# SDRAM.net
KiCad netlist of a schematic drawn in Altium Designer
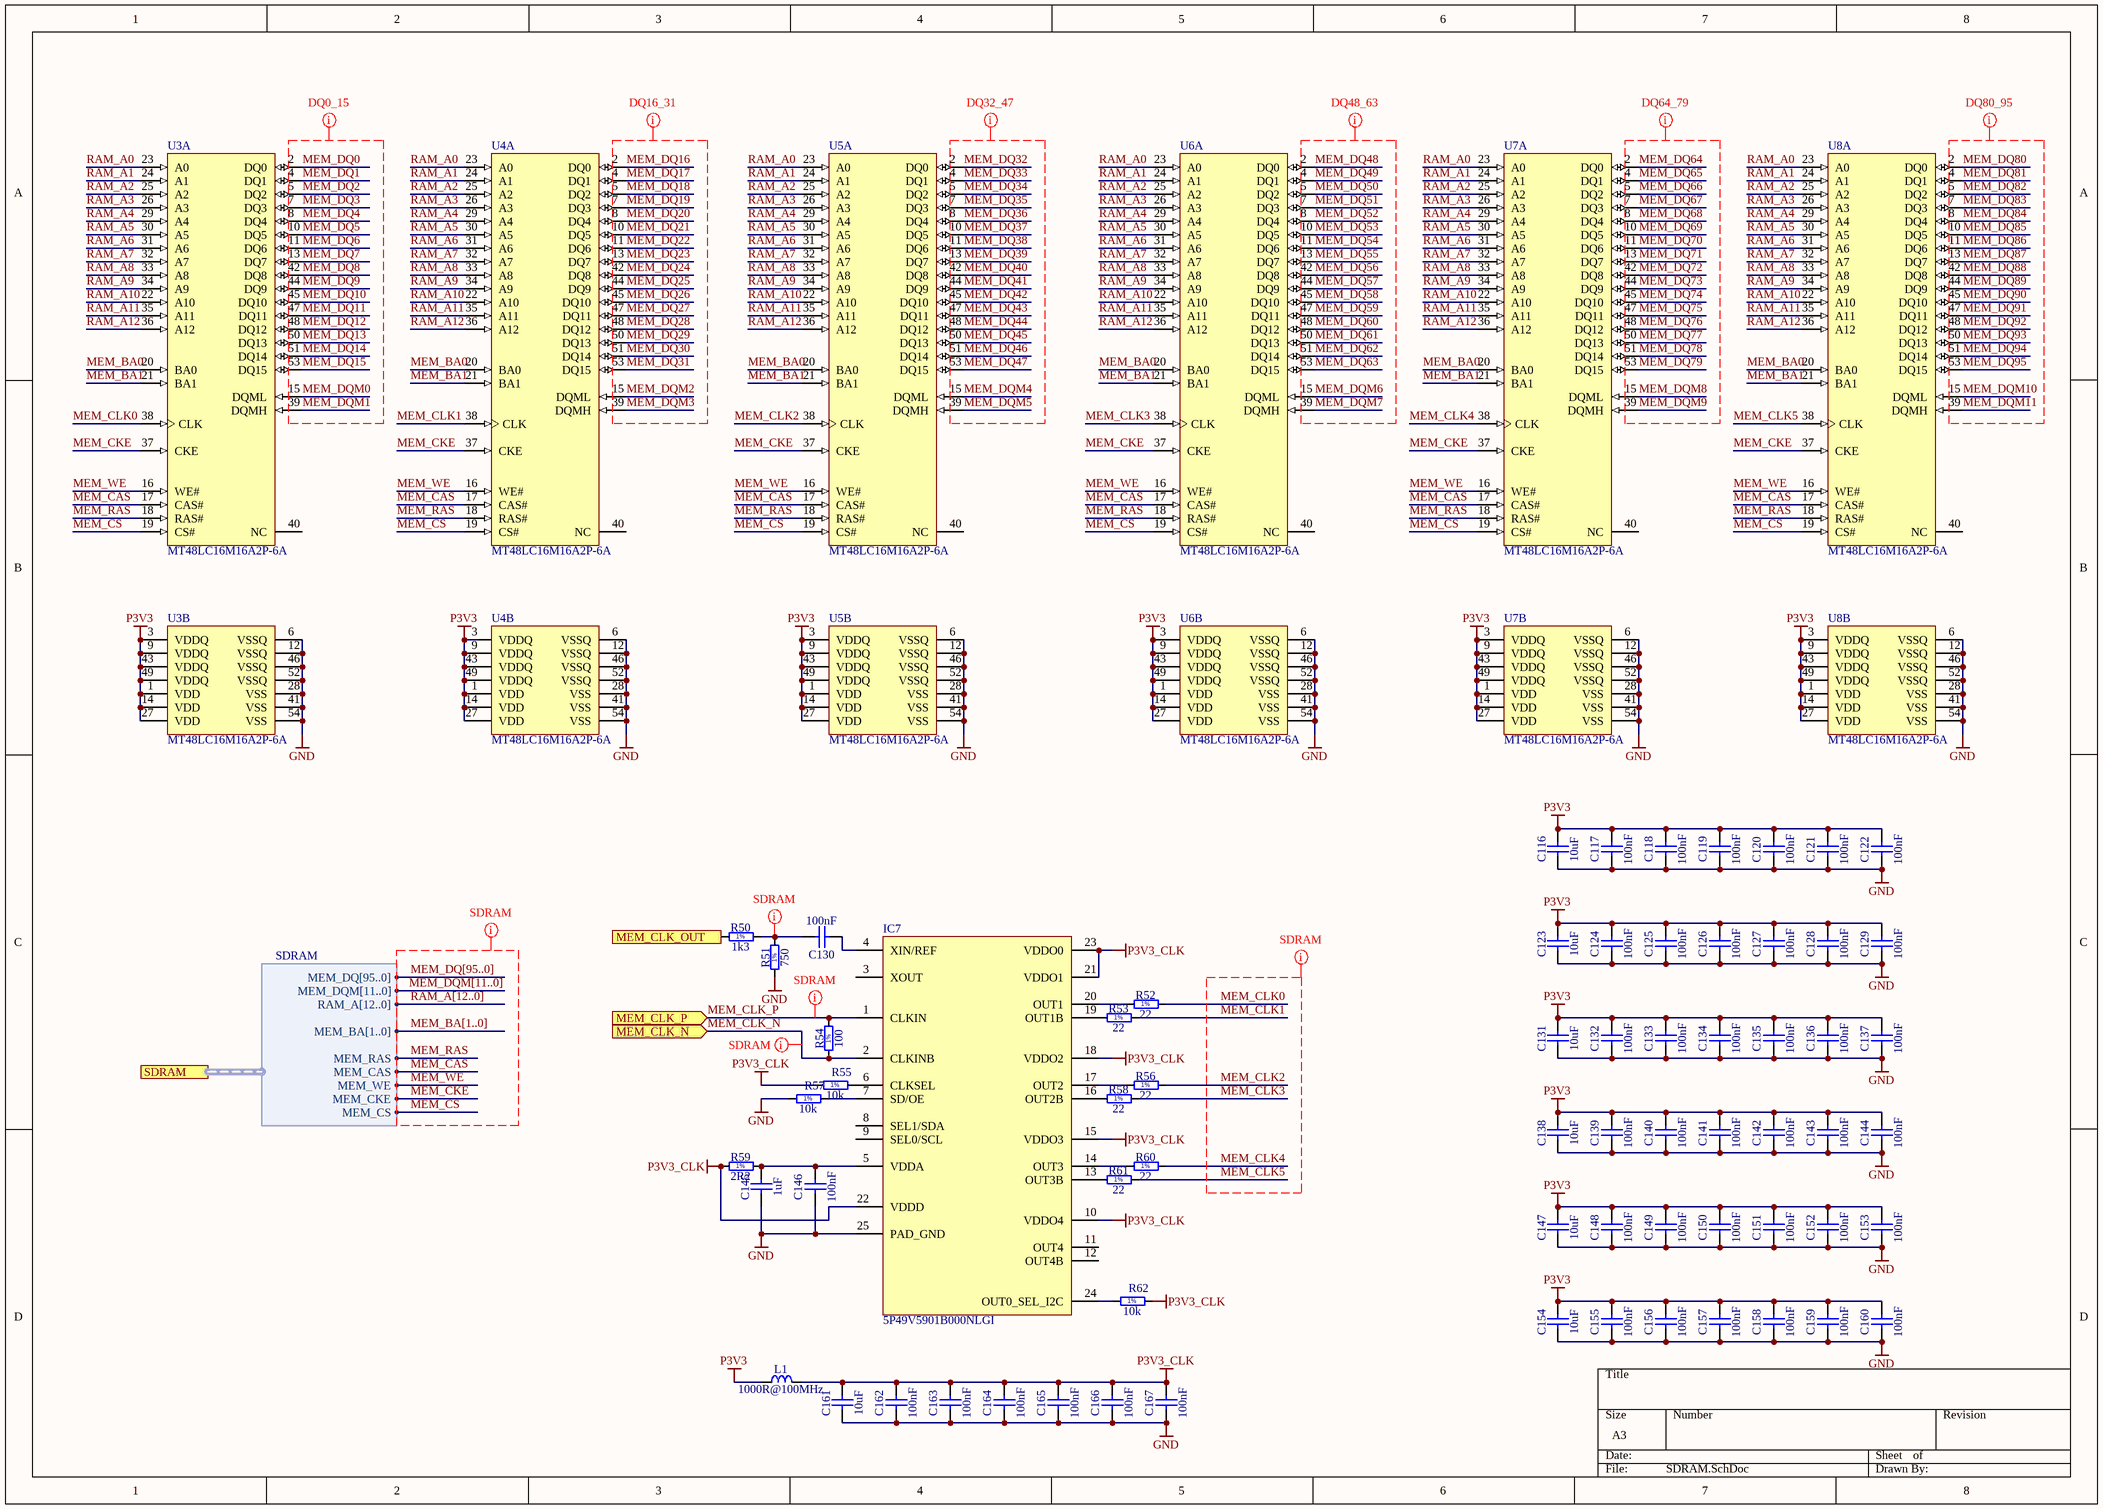
[diagram p0: SDRAM.SchDoc]

(export (version "E")
  (design (tool "Eeschema 10.0.6"))
  (components
    (comp (ref "C116")
      (value "10uF")
      (footprint "CAPC2012X135N")
      (description "Non-polarised capacitor")
      (fields
        (field (name "PART NUMBER") "CC0805_10UF_16V_10%_X5R")
        (field (name "VOLTAGE") "16V")
        (field (name "AUTHOR") "CERN DEM JLC")
      )
      (libsource (lib "Capacitors") (part "Capacitor - non polarized"))
    )
    (comp (ref "C117")
      (value "100nF")
      (footprint "CAPC0603X33N")
      (description "Non-polarised capacitor")
      (fields
        (field (name "MANUFACTURER") "GENERIC")
        (field (name "PART NUMBER") "CC0201_100NF_6.3V_10%_X5R")
        (field (name "AUTHOR") "CERN DEM JLC")
      )
      (libsource (lib "Capacitors") (part "Capacitor - non polarized"))
    )
    (comp (ref "C118")
      (value "100nF")
      (footprint "CAPC0603X33N")
      (description "Non-polarised capacitor")
      (fields
        (field (name "MANUFACTURER") "GENERIC")
        (field (name "PART NUMBER") "CC0201_100NF_6.3V_10%_X5R")
        (field (name "AUTHOR") "CERN DEM JLC")
      )
      (libsource (lib "Capacitors") (part "Capacitor - non polarized"))
    )
    (comp (ref "C119")
      (value "100nF")
      (footprint "CAPC0603X33N")
      (description "Non-polarised capacitor")
      (fields
        (field (name "MANUFACTURER") "GENERIC")
        (field (name "PART NUMBER") "CC0201_100NF_6.3V_10%_X5R")
        (field (name "AUTHOR") "CERN DEM JLC")
      )
      (libsource (lib "Capacitors") (part "Capacitor - non polarized"))
    )
    (comp (ref "C120")
      (value "100nF")
      (footprint "CAPC0603X33N")
      (description "Non-polarised capacitor")
      (fields
        (field (name "MANUFACTURER") "GENERIC")
        (field (name "PART NUMBER") "CC0201_100NF_6.3V_10%_X5R")
        (field (name "AUTHOR") "CERN DEM JLC")
      )
      (libsource (lib "Capacitors") (part "Capacitor - non polarized"))
    )
    (comp (ref "C121")
      (value "100nF")
      (footprint "CAPC0603X33N")
      (description "Non-polarised capacitor")
      (fields
        (field (name "MANUFACTURER") "GENERIC")
        (field (name "PART NUMBER") "CC0201_100NF_6.3V_10%_X5R")
        (field (name "AUTHOR") "CERN DEM JLC")
      )
      (libsource (lib "Capacitors") (part "Capacitor - non polarized"))
    )
    (comp (ref "C122")
      (value "100nF")
      (footprint "CAPC0603X33N")
      (description "Non-polarised capacitor")
      (fields
        (field (name "MANUFACTURER") "GENERIC")
        (field (name "PART NUMBER") "CC0201_100NF_6.3V_10%_X5R")
        (field (name "AUTHOR") "CERN DEM JLC")
      )
      (libsource (lib "Capacitors") (part "Capacitor - non polarized"))
    )
    (comp (ref "C123")
      (value "10uF")
      (footprint "CAPC2012X135N")
      (description "Non-polarised capacitor")
      (fields
        (field (name "PART NUMBER") "CC0805_10UF_16V_10%_X5R")
        (field (name "VOLTAGE") "16V")
        (field (name "AUTHOR") "CERN DEM JLC")
      )
      (libsource (lib "Capacitors") (part "Capacitor - non polarized"))
    )
    (comp (ref "C124")
      (value "100nF")
      (footprint "CAPC0603X33N")
      (description "Non-polarised capacitor")
      (fields
        (field (name "MANUFACTURER") "GENERIC")
        (field (name "PART NUMBER") "CC0201_100NF_6.3V_10%_X5R")
        (field (name "AUTHOR") "CERN DEM JLC")
      )
      (libsource (lib "Capacitors") (part "Capacitor - non polarized"))
    )
    (comp (ref "C125")
      (value "100nF")
      (footprint "CAPC0603X33N")
      (description "Non-polarised capacitor")
      (fields
        (field (name "MANUFACTURER") "GENERIC")
        (field (name "PART NUMBER") "CC0201_100NF_6.3V_10%_X5R")
        (field (name "AUTHOR") "CERN DEM JLC")
      )
      (libsource (lib "Capacitors") (part "Capacitor - non polarized"))
    )
    (comp (ref "C126")
      (value "100nF")
      (footprint "CAPC0603X33N")
      (description "Non-polarised capacitor")
      (fields
        (field (name "MANUFACTURER") "GENERIC")
        (field (name "PART NUMBER") "CC0201_100NF_6.3V_10%_X5R")
        (field (name "AUTHOR") "CERN DEM JLC")
      )
      (libsource (lib "Capacitors") (part "Capacitor - non polarized"))
    )
    (comp (ref "C127")
      (value "100nF")
      (footprint "CAPC0603X33N")
      (description "Non-polarised capacitor")
      (fields
        (field (name "MANUFACTURER") "GENERIC")
        (field (name "PART NUMBER") "CC0201_100NF_6.3V_10%_X5R")
        (field (name "AUTHOR") "CERN DEM JLC")
      )
      (libsource (lib "Capacitors") (part "Capacitor - non polarized"))
    )
    (comp (ref "C128")
      (value "100nF")
      (footprint "CAPC0603X33N")
      (description "Non-polarised capacitor")
      (fields
        (field (name "MANUFACTURER") "GENERIC")
        (field (name "PART NUMBER") "CC0201_100NF_6.3V_10%_X5R")
        (field (name "AUTHOR") "CERN DEM JLC")
      )
      (libsource (lib "Capacitors") (part "Capacitor - non polarized"))
    )
    (comp (ref "C129")
      (value "100nF")
      (footprint "CAPC0603X33N")
      (description "Non-polarised capacitor")
      (fields
        (field (name "MANUFACTURER") "GENERIC")
        (field (name "PART NUMBER") "CC0201_100NF_6.3V_10%_X5R")
        (field (name "AUTHOR") "CERN DEM JLC")
      )
      (libsource (lib "Capacitors") (part "Capacitor - non polarized"))
    )
    (comp (ref "C130")
      (value "100nF")
      (footprint "CAPC0603X33N")
      (description "Non-polarised capacitor")
      (fields
        (field (name "MANUFACTURER") "GENERIC")
        (field (name "PART NUMBER") "CC0201_100NF_6.3V_10%_X5R")
        (field (name "AUTHOR") "CERN DEM JLC")
      )
      (libsource (lib "Capacitors") (part "Capacitor - non polarized"))
    )
    (comp (ref "C131")
      (value "10uF")
      (footprint "CAPC2012X135N")
      (description "Non-polarised capacitor")
      (fields
        (field (name "PART NUMBER") "CC0805_10UF_16V_10%_X5R")
        (field (name "VOLTAGE") "16V")
        (field (name "AUTHOR") "CERN DEM JLC")
      )
      (libsource (lib "Capacitors") (part "Capacitor - non polarized"))
    )
    (comp (ref "C132")
      (value "100nF")
      (footprint "CAPC0603X33N")
      (description "Non-polarised capacitor")
      (fields
        (field (name "MANUFACTURER") "GENERIC")
        (field (name "PART NUMBER") "CC0201_100NF_6.3V_10%_X5R")
        (field (name "AUTHOR") "CERN DEM JLC")
      )
      (libsource (lib "Capacitors") (part "Capacitor - non polarized"))
    )
    (comp (ref "C133")
      (value "100nF")
      (footprint "CAPC0603X33N")
      (description "Non-polarised capacitor")
      (fields
        (field (name "MANUFACTURER") "GENERIC")
        (field (name "PART NUMBER") "CC0201_100NF_6.3V_10%_X5R")
        (field (name "AUTHOR") "CERN DEM JLC")
      )
      (libsource (lib "Capacitors") (part "Capacitor - non polarized"))
    )
    (comp (ref "C134")
      (value "100nF")
      (footprint "CAPC0603X33N")
      (description "Non-polarised capacitor")
      (fields
        (field (name "MANUFACTURER") "GENERIC")
        (field (name "PART NUMBER") "CC0201_100NF_6.3V_10%_X5R")
        (field (name "AUTHOR") "CERN DEM JLC")
      )
      (libsource (lib "Capacitors") (part "Capacitor - non polarized"))
    )
    (comp (ref "C135")
      (value "100nF")
      (footprint "CAPC0603X33N")
      (description "Non-polarised capacitor")
      (fields
        (field (name "MANUFACTURER") "GENERIC")
        (field (name "PART NUMBER") "CC0201_100NF_6.3V_10%_X5R")
        (field (name "AUTHOR") "CERN DEM JLC")
      )
      (libsource (lib "Capacitors") (part "Capacitor - non polarized"))
    )
    (comp (ref "C136")
      (value "100nF")
      (footprint "CAPC0603X33N")
      (description "Non-polarised capacitor")
      (fields
        (field (name "MANUFACTURER") "GENERIC")
        (field (name "PART NUMBER") "CC0201_100NF_6.3V_10%_X5R")
        (field (name "AUTHOR") "CERN DEM JLC")
      )
      (libsource (lib "Capacitors") (part "Capacitor - non polarized"))
    )
    (comp (ref "C137")
      (value "100nF")
      (footprint "CAPC0603X33N")
      (description "Non-polarised capacitor")
      (fields
        (field (name "MANUFACTURER") "GENERIC")
        (field (name "PART NUMBER") "CC0201_100NF_6.3V_10%_X5R")
        (field (name "AUTHOR") "CERN DEM JLC")
      )
      (libsource (lib "Capacitors") (part "Capacitor - non polarized"))
    )
    (comp (ref "C138")
      (value "10uF")
      (footprint "CAPC2012X135N")
      (description "Non-polarised capacitor")
      (fields
        (field (name "PART NUMBER") "CC0805_10UF_16V_10%_X5R")
        (field (name "VOLTAGE") "16V")
        (field (name "AUTHOR") "CERN DEM JLC")
      )
      (libsource (lib "Capacitors") (part "Capacitor - non polarized"))
    )
    (comp (ref "C139")
      (value "100nF")
      (footprint "CAPC0603X33N")
      (description "Non-polarised capacitor")
      (fields
        (field (name "MANUFACTURER") "GENERIC")
        (field (name "PART NUMBER") "CC0201_100NF_6.3V_10%_X5R")
        (field (name "AUTHOR") "CERN DEM JLC")
      )
      (libsource (lib "Capacitors") (part "Capacitor - non polarized"))
    )
    (comp (ref "C140")
      (value "100nF")
      (footprint "CAPC0603X33N")
      (description "Non-polarised capacitor")
      (fields
        (field (name "MANUFACTURER") "GENERIC")
        (field (name "PART NUMBER") "CC0201_100NF_6.3V_10%_X5R")
        (field (name "AUTHOR") "CERN DEM JLC")
      )
      (libsource (lib "Capacitors") (part "Capacitor - non polarized"))
    )
    (comp (ref "C141")
      (value "100nF")
      (footprint "CAPC0603X33N")
      (description "Non-polarised capacitor")
      (fields
        (field (name "MANUFACTURER") "GENERIC")
        (field (name "PART NUMBER") "CC0201_100NF_6.3V_10%_X5R")
        (field (name "AUTHOR") "CERN DEM JLC")
      )
      (libsource (lib "Capacitors") (part "Capacitor - non polarized"))
    )
    (comp (ref "C142")
      (value "100nF")
      (footprint "CAPC0603X33N")
      (description "Non-polarised capacitor")
      (fields
        (field (name "MANUFACTURER") "GENERIC")
        (field (name "PART NUMBER") "CC0201_100NF_6.3V_10%_X5R")
        (field (name "AUTHOR") "CERN DEM JLC")
      )
      (libsource (lib "Capacitors") (part "Capacitor - non polarized"))
    )
    (comp (ref "C143")
      (value "100nF")
      (footprint "CAPC0603X33N")
      (description "Non-polarised capacitor")
      (fields
        (field (name "MANUFACTURER") "GENERIC")
        (field (name "PART NUMBER") "CC0201_100NF_6.3V_10%_X5R")
        (field (name "AUTHOR") "CERN DEM JLC")
      )
      (libsource (lib "Capacitors") (part "Capacitor - non polarized"))
    )
    (comp (ref "C144")
      (value "100nF")
      (footprint "CAPC0603X33N")
      (description "Non-polarised capacitor")
      (fields
        (field (name "MANUFACTURER") "GENERIC")
        (field (name "PART NUMBER") "CC0201_100NF_6.3V_10%_X5R")
        (field (name "AUTHOR") "CERN DEM JLC")
      )
      (libsource (lib "Capacitors") (part "Capacitor - non polarized"))
    )
    (comp (ref "C145")
      (value "1uF")
      (footprint "CAPC1005X55N")
      (description "Non-polarised capacitor")
      (fields
        (field (name "PART NUMBER") "CC0402_1UF_16V_10%_X5R")
        (field (name "VOLTAGE") "16V")
        (field (name "AUTHOR") "CERN DEM JLC")
      )
      (libsource (lib "Capacitors") (part "Capacitor - non polarized"))
    )
    (comp (ref "C146")
      (value "100nF")
      (footprint "CAPC0603X33N")
      (description "Non-polarised capacitor")
      (fields
        (field (name "MANUFACTURER") "GENERIC")
        (field (name "PART NUMBER") "CC0201_100NF_6.3V_10%_X5R")
        (field (name "AUTHOR") "CERN DEM JLC")
      )
      (libsource (lib "Capacitors") (part "Capacitor - non polarized"))
    )
    (comp (ref "C147")
      (value "10uF")
      (footprint "CAPC2012X135N")
      (description "Non-polarised capacitor")
      (fields
        (field (name "PART NUMBER") "CC0805_10UF_16V_10%_X5R")
        (field (name "VOLTAGE") "16V")
        (field (name "AUTHOR") "CERN DEM JLC")
      )
      (libsource (lib "Capacitors") (part "Capacitor - non polarized"))
    )
    (comp (ref "C148")
      (value "100nF")
      (footprint "CAPC0603X33N")
      (description "Non-polarised capacitor")
      (fields
        (field (name "MANUFACTURER") "GENERIC")
        (field (name "PART NUMBER") "CC0201_100NF_6.3V_10%_X5R")
        (field (name "AUTHOR") "CERN DEM JLC")
      )
      (libsource (lib "Capacitors") (part "Capacitor - non polarized"))
    )
    (comp (ref "C149")
      (value "100nF")
      (footprint "CAPC0603X33N")
      (description "Non-polarised capacitor")
      (fields
        (field (name "MANUFACTURER") "GENERIC")
        (field (name "PART NUMBER") "CC0201_100NF_6.3V_10%_X5R")
        (field (name "AUTHOR") "CERN DEM JLC")
      )
      (libsource (lib "Capacitors") (part "Capacitor - non polarized"))
    )
    (comp (ref "C150")
      (value "100nF")
      (footprint "CAPC0603X33N")
      (description "Non-polarised capacitor")
      (fields
        (field (name "MANUFACTURER") "GENERIC")
        (field (name "PART NUMBER") "CC0201_100NF_6.3V_10%_X5R")
        (field (name "AUTHOR") "CERN DEM JLC")
      )
      (libsource (lib "Capacitors") (part "Capacitor - non polarized"))
    )
    (comp (ref "C151")
      (value "100nF")
      (footprint "CAPC0603X33N")
      (description "Non-polarised capacitor")
      (fields
        (field (name "MANUFACTURER") "GENERIC")
        (field (name "PART NUMBER") "CC0201_100NF_6.3V_10%_X5R")
        (field (name "AUTHOR") "CERN DEM JLC")
      )
      (libsource (lib "Capacitors") (part "Capacitor - non polarized"))
    )
    (comp (ref "C152")
      (value "100nF")
      (footprint "CAPC0603X33N")
      (description "Non-polarised capacitor")
      (fields
        (field (name "MANUFACTURER") "GENERIC")
        (field (name "PART NUMBER") "CC0201_100NF_6.3V_10%_X5R")
        (field (name "AUTHOR") "CERN DEM JLC")
      )
      (libsource (lib "Capacitors") (part "Capacitor - non polarized"))
    )
    (comp (ref "C153")
      (value "100nF")
      (footprint "CAPC0603X33N")
      (description "Non-polarised capacitor")
      (fields
        (field (name "MANUFACTURER") "GENERIC")
        (field (name "PART NUMBER") "CC0201_100NF_6.3V_10%_X5R")
        (field (name "AUTHOR") "CERN DEM JLC")
      )
      (libsource (lib "Capacitors") (part "Capacitor - non polarized"))
    )
    (comp (ref "C154")
      (value "10uF")
      (footprint "CAPC2012X135N")
      (description "Non-polarised capacitor")
      (fields
        (field (name "PART NUMBER") "CC0805_10UF_16V_10%_X5R")
        (field (name "VOLTAGE") "16V")
        (field (name "AUTHOR") "CERN DEM JLC")
      )
      (libsource (lib "Capacitors") (part "Capacitor - non polarized"))
    )
    (comp (ref "C155")
      (value "100nF")
      (footprint "CAPC0603X33N")
      (description "Non-polarised capacitor")
      (fields
        (field (name "MANUFACTURER") "GENERIC")
        (field (name "PART NUMBER") "CC0201_100NF_6.3V_10%_X5R")
        (field (name "AUTHOR") "CERN DEM JLC")
      )
      (libsource (lib "Capacitors") (part "Capacitor - non polarized"))
    )
    (comp (ref "C156")
      (value "100nF")
      (footprint "CAPC0603X33N")
      (description "Non-polarised capacitor")
      (fields
        (field (name "MANUFACTURER") "GENERIC")
        (field (name "PART NUMBER") "CC0201_100NF_6.3V_10%_X5R")
        (field (name "AUTHOR") "CERN DEM JLC")
      )
      (libsource (lib "Capacitors") (part "Capacitor - non polarized"))
    )
    (comp (ref "C157")
      (value "100nF")
      (footprint "CAPC0603X33N")
      (description "Non-polarised capacitor")
      (fields
        (field (name "MANUFACTURER") "GENERIC")
        (field (name "PART NUMBER") "CC0201_100NF_6.3V_10%_X5R")
        (field (name "AUTHOR") "CERN DEM JLC")
      )
      (libsource (lib "Capacitors") (part "Capacitor - non polarized"))
    )
    (comp (ref "C158")
      (value "100nF")
      (footprint "CAPC0603X33N")
      (description "Non-polarised capacitor")
      (fields
        (field (name "MANUFACTURER") "GENERIC")
        (field (name "PART NUMBER") "CC0201_100NF_6.3V_10%_X5R")
        (field (name "AUTHOR") "CERN DEM JLC")
      )
      (libsource (lib "Capacitors") (part "Capacitor - non polarized"))
    )
    (comp (ref "C159")
      (value "100nF")
      (footprint "CAPC0603X33N")
      (description "Non-polarised capacitor")
      (fields
        (field (name "MANUFACTURER") "GENERIC")
        (field (name "PART NUMBER") "CC0201_100NF_6.3V_10%_X5R")
        (field (name "AUTHOR") "CERN DEM JLC")
      )
      (libsource (lib "Capacitors") (part "Capacitor - non polarized"))
    )
    (comp (ref "C160")
      (value "100nF")
      (footprint "CAPC0603X33N")
      (description "Non-polarised capacitor")
      (fields
        (field (name "MANUFACTURER") "GENERIC")
        (field (name "PART NUMBER") "CC0201_100NF_6.3V_10%_X5R")
        (field (name "AUTHOR") "CERN DEM JLC")
      )
      (libsource (lib "Capacitors") (part "Capacitor - non polarized"))
    )
    (comp (ref "C161")
      (value "10uF")
      (footprint "CAPC2012X135N")
      (description "Non-polarised capacitor")
      (fields
        (field (name "PART NUMBER") "CC0805_10UF_16V_10%_X5R")
        (field (name "VOLTAGE") "16V")
        (field (name "AUTHOR") "CERN DEM JLC")
      )
      (libsource (lib "Capacitors") (part "Capacitor - non polarized"))
    )
    (comp (ref "C162")
      (value "100nF")
      (footprint "CAPC0603X33N")
      (description "Non-polarised capacitor")
      (fields
        (field (name "MANUFACTURER") "GENERIC")
        (field (name "PART NUMBER") "CC0201_100NF_6.3V_10%_X5R")
        (field (name "AUTHOR") "CERN DEM JLC")
      )
      (libsource (lib "Capacitors") (part "Capacitor - non polarized"))
    )
    (comp (ref "C163")
      (value "100nF")
      (footprint "CAPC0603X33N")
      (description "Non-polarised capacitor")
      (fields
        (field (name "MANUFACTURER") "GENERIC")
        (field (name "PART NUMBER") "CC0201_100NF_6.3V_10%_X5R")
        (field (name "AUTHOR") "CERN DEM JLC")
      )
      (libsource (lib "Capacitors") (part "Capacitor - non polarized"))
    )
    (comp (ref "C164")
      (value "100nF")
      (footprint "CAPC0603X33N")
      (description "Non-polarised capacitor")
      (fields
        (field (name "MANUFACTURER") "GENERIC")
        (field (name "PART NUMBER") "CC0201_100NF_6.3V_10%_X5R")
        (field (name "AUTHOR") "CERN DEM JLC")
      )
      (libsource (lib "Capacitors") (part "Capacitor - non polarized"))
    )
    (comp (ref "C165")
      (value "100nF")
      (footprint "CAPC0603X33N")
      (description "Non-polarised capacitor")
      (fields
        (field (name "MANUFACTURER") "GENERIC")
        (field (name "PART NUMBER") "CC0201_100NF_6.3V_10%_X5R")
        (field (name "AUTHOR") "CERN DEM JLC")
      )
      (libsource (lib "Capacitors") (part "Capacitor - non polarized"))
    )
    (comp (ref "C166")
      (value "100nF")
      (footprint "CAPC0603X33N")
      (description "Non-polarised capacitor")
      (fields
        (field (name "MANUFACTURER") "GENERIC")
        (field (name "PART NUMBER") "CC0201_100NF_6.3V_10%_X5R")
        (field (name "AUTHOR") "CERN DEM JLC")
      )
      (libsource (lib "Capacitors") (part "Capacitor - non polarized"))
    )
    (comp (ref "C167")
      (value "100nF")
      (footprint "CAPC0603X33N")
      (description "Non-polarised capacitor")
      (fields
        (field (name "MANUFACTURER") "GENERIC")
        (field (name "PART NUMBER") "CC0201_100NF_6.3V_10%_X5R")
        (field (name "AUTHOR") "CERN DEM JLC")
      )
      (libsource (lib "Capacitors") (part "Capacitor - non polarized"))
    )
    (comp (ref "IC7")
      (value "5P49V5901B000NLGI")
      (footprint "QFN50P400X400X100-25N-S280")
      (libsource (lib "MG_lib") (part "5P49V5901B000NLGI"))
    )
    (comp (ref "L1")
      (value "1000R@100MHz")
      (footprint "INDC1608X95N")
      (description "Inductor")
      (fields
        (field (name "PART NUMBER") "IND0603_MURATA_BLM18HE102SN1")
        (field (name "POWER") "600mA")
        (field (name "AUTHOR") "CERN DEM JLC")
      )
      (libsource (lib "Inductors & Transformers") (part "Inductor"))
    )
    (comp (ref "R50")
      (value "1k3")
      (footprint "RESC1005X40N")
      (description "Resistor - 1%")
      (fields
        (field (name "PART NUMBER") "R0402_1K3_1%_0.0625W_100PPM")
        (field (name "POWER") "0.0625W")
        (field (name "AUTHOR") "CERN DEM JLC")
      )
      (libsource (lib "Resistors") (part "Resistor - 1%"))
    )
    (comp (ref "R51")
      (value "750")
      (footprint "RESC1005X40N")
      (description "Resistor - 1%")
      (fields
        (field (name "PART NUMBER") "R0402_750R_1%_0.0625W_100PPM")
        (field (name "POWER") "0.0625W")
        (field (name "AUTHOR") "CERN DEM JLC")
      )
      (libsource (lib "Resistors") (part "Resistor - 1%"))
    )
    (comp (ref "R52")
      (value "22")
      (footprint "RESC1005X40N")
      (description "Resistor - 1%")
      (fields
        (field (name "PART NUMBER") "R0402_22R_1%_0.0625W_100PPM")
        (field (name "POWER") "0.0625W")
        (field (name "AUTHOR") "CERN DEM JLC")
      )
      (libsource (lib "Resistors") (part "Resistor - 1%"))
    )
    (comp (ref "R53")
      (value "22")
      (footprint "RESC1005X40N")
      (description "Resistor - 1%")
      (fields
        (field (name "PART NUMBER") "R0402_22R_1%_0.0625W_100PPM")
        (field (name "POWER") "0.0625W")
        (field (name "AUTHOR") "CERN DEM JLC")
      )
      (libsource (lib "Resistors") (part "Resistor - 1%"))
    )
    (comp (ref "R54")
      (value "100")
      (footprint "RESC1005X40N")
      (description "Resistor - 1%")
      (fields
        (field (name "PART NUMBER") "R0402_100R_1%_0.0625W_100PPM")
        (field (name "POWER") "0.0625W")
        (field (name "AUTHOR") "CERN DEM JLC")
      )
      (libsource (lib "Resistors") (part "Resistor - 1%"))
    )
    (comp (ref "R55")
      (value "10k")
      (footprint "RESC1005X40N")
      (description "Resistor - 1%")
      (fields
        (field (name "MANUFACTURER PART NUMBER") "R0402_10K_1%_0.0625W_100PPM")
        (field (name "MANUFACTURER") "GENERIC")
        (field (name "AUTHOR") "CERN DEM JLC")
      )
      (libsource (lib "Resistors") (part "Resistor - 1%"))
    )
    (comp (ref "R56")
      (value "22")
      (footprint "RESC1005X40N")
      (description "Resistor - 1%")
      (fields
        (field (name "PART NUMBER") "R0402_22R_1%_0.0625W_100PPM")
        (field (name "POWER") "0.0625W")
        (field (name "AUTHOR") "CERN DEM JLC")
      )
      (libsource (lib "Resistors") (part "Resistor - 1%"))
    )
    (comp (ref "R57")
      (value "10k")
      (footprint "RESC1005X40N")
      (description "Resistor - 1%")
      (fields
        (field (name "MANUFACTURER PART NUMBER") "R0402_10K_1%_0.0625W_100PPM")
        (field (name "MANUFACTURER") "GENERIC")
        (field (name "AUTHOR") "CERN DEM JLC")
      )
      (libsource (lib "Resistors") (part "Resistor - 1%"))
    )
    (comp (ref "R58")
      (value "22")
      (footprint "RESC1005X40N")
      (description "Resistor - 1%")
      (fields
        (field (name "PART NUMBER") "R0402_22R_1%_0.0625W_100PPM")
        (field (name "POWER") "0.0625W")
        (field (name "AUTHOR") "CERN DEM JLC")
      )
      (libsource (lib "Resistors") (part "Resistor - 1%"))
    )
    (comp (ref "R59")
      (value "2R2")
      (footprint "RESC1005X40N")
      (description "Resistor - 1%")
      (fields
        (field (name "PART NUMBER") "R0402_2R2_1%_0.0625W_200PPM")
        (field (name "POWER") "0.0625W")
        (field (name "AUTHOR") "CERN DEM JLC")
      )
      (libsource (lib "Resistors") (part "Resistor - 1%"))
    )
    (comp (ref "R60")
      (value "22")
      (footprint "RESC1005X40N")
      (description "Resistor - 1%")
      (fields
        (field (name "PART NUMBER") "R0402_22R_1%_0.0625W_100PPM")
        (field (name "POWER") "0.0625W")
        (field (name "AUTHOR") "CERN DEM JLC")
      )
      (libsource (lib "Resistors") (part "Resistor - 1%"))
    )
    (comp (ref "R61")
      (value "22")
      (footprint "RESC1005X40N")
      (description "Resistor - 1%")
      (fields
        (field (name "PART NUMBER") "R0402_22R_1%_0.0625W_100PPM")
        (field (name "POWER") "0.0625W")
        (field (name "AUTHOR") "CERN DEM JLC")
      )
      (libsource (lib "Resistors") (part "Resistor - 1%"))
    )
    (comp (ref "R62")
      (value "10k")
      (footprint "RESC1005X40N")
      (description "Resistor - 1%")
      (fields
        (field (name "MANUFACTURER PART NUMBER") "R0402_10K_1%_0.0625W_100PPM")
        (field (name "MANUFACTURER") "GENERIC")
        (field (name "AUTHOR") "CERN DEM JLC")
      )
      (libsource (lib "Resistors") (part "Resistor - 1%"))
    )
    (comp (ref "U3")
      (value "MT48LC16M16A2P-6A")
      (footprint "MICT-P-54_N")
      (description "256Mb PC133 SDR SDRAM, 16Mb x 16, 6ns, 3.3V, 0 to 70 degC, 54-Pin TSOP, Pb-Free")
      (fields (field (name "MANUFACTURER") "Micron") (field (name "VOLTAGE") "3.3VÂ "))
      (libsource (lib "Altium Content Vault") (part "MICT-MT48LC16M16A2P-54"))
    )
    (comp (ref "U4")
      (value "MT48LC16M16A2P-6A")
      (footprint "MICT-P-54_N")
      (description "256Mb PC133 SDR SDRAM, 16Mb x 16, 6ns, 3.3V, 0 to 70 degC, 54-Pin TSOP, Pb-Free")
      (fields (field (name "MANUFACTURER") "Micron") (field (name "VOLTAGE") "3.3VÂ "))
      (libsource (lib "Altium Content Vault") (part "MICT-MT48LC16M16A2P-54"))
    )
    (comp (ref "U5")
      (value "MT48LC16M16A2P-6A")
      (footprint "MICT-P-54_N")
      (description "256Mb PC133 SDR SDRAM, 16Mb x 16, 6ns, 3.3V, 0 to 70 degC, 54-Pin TSOP, Pb-Free")
      (fields (field (name "MANUFACTURER") "Micron") (field (name "VOLTAGE") "3.3VÂ "))
      (libsource (lib "Altium Content Vault") (part "MICT-MT48LC16M16A2P-54"))
    )
    (comp (ref "U6")
      (value "MT48LC16M16A2P-6A")
      (footprint "MICT-P-54_N")
      (description "256Mb PC133 SDR SDRAM, 16Mb x 16, 6ns, 3.3V, 0 to 70 degC, 54-Pin TSOP, Pb-Free")
      (fields (field (name "MANUFACTURER") "Micron") (field (name "VOLTAGE") "3.3VÂ "))
      (libsource (lib "Altium Content Vault") (part "MICT-MT48LC16M16A2P-54"))
    )
    (comp (ref "U7")
      (value "MT48LC16M16A2P-6A")
      (footprint "MICT-P-54_N")
      (description "256Mb PC133 SDR SDRAM, 16Mb x 16, 6ns, 3.3V, 0 to 70 degC, 54-Pin TSOP, Pb-Free")
      (fields (field (name "MANUFACTURER") "Micron") (field (name "VOLTAGE") "3.3VÂ "))
      (libsource (lib "Altium Content Vault") (part "MICT-MT48LC16M16A2P-54"))
    )
    (comp (ref "U8")
      (value "MT48LC16M16A2P-6A")
      (footprint "MICT-P-54_N")
      (description "256Mb PC133 SDR SDRAM, 16Mb x 16, 6ns, 3.3V, 0 to 70 degC, 54-Pin TSOP, Pb-Free")
      (fields (field (name "MANUFACTURER") "Micron") (field (name "VOLTAGE") "3.3VÂ "))
      (libsource (lib "Altium Content Vault") (part "MICT-MT48LC16M16A2P-54"))
    )
  )
  (nets
    (net (code "2") (name "/MEM_BA0") (class "Default")
      (node (ref "U3") (pin "20") (pinfunction "BA0_20") (pintype "input"))
      (node (ref "U4") (pin "20") (pinfunction "BA0_20") (pintype "input"))
      (node (ref "U5") (pin "20") (pinfunction "BA0_20") (pintype "input"))
      (node (ref "U6") (pin "20") (pinfunction "BA0_20") (pintype "input"))
      (node (ref "U7") (pin "20") (pinfunction "BA0_20") (pintype "input"))
      (node (ref "U8") (pin "20") (pinfunction "BA0_20") (pintype "input"))
    )
    (net (code "3") (name "/MEM_BA1") (class "Default")
      (node (ref "U3") (pin "21") (pinfunction "BA1_21") (pintype "input"))
      (node (ref "U4") (pin "21") (pinfunction "BA1_21") (pintype "input"))
      (node (ref "U5") (pin "21") (pinfunction "BA1_21") (pintype "input"))
      (node (ref "U6") (pin "21") (pinfunction "BA1_21") (pintype "input"))
      (node (ref "U7") (pin "21") (pinfunction "BA1_21") (pintype "input"))
      (node (ref "U8") (pin "21") (pinfunction "BA1_21") (pintype "input"))
    )
    (net (code "4") (name "/MEM_CAS") (class "Default")
      (node (ref "U3") (pin "17") (pinfunction "CAS#_17") (pintype "input"))
      (node (ref "U4") (pin "17") (pinfunction "CAS#_17") (pintype "input"))
      (node (ref "U5") (pin "17") (pinfunction "CAS#_17") (pintype "input"))
      (node (ref "U6") (pin "17") (pinfunction "CAS#_17") (pintype "input"))
      (node (ref "U7") (pin "17") (pinfunction "CAS#_17") (pintype "input"))
      (node (ref "U8") (pin "17") (pinfunction "CAS#_17") (pintype "input"))
    )
    (net (code "5") (name "/MEM_CKE") (class "Default")
      (node (ref "U3") (pin "37") (pinfunction "CKE_37") (pintype "input"))
      (node (ref "U4") (pin "37") (pinfunction "CKE_37") (pintype "input"))
      (node (ref "U5") (pin "37") (pinfunction "CKE_37") (pintype "input"))
      (node (ref "U6") (pin "37") (pinfunction "CKE_37") (pintype "input"))
      (node (ref "U7") (pin "37") (pinfunction "CKE_37") (pintype "input"))
      (node (ref "U8") (pin "37") (pinfunction "CKE_37") (pintype "input"))
    )
    (net (code "6") (name "/MEM_CLK0") (class "Default")
      (node (ref "R52") (pin "2") (pinfunction "2_2") (pintype "passive"))
      (node (ref "U3") (pin "38") (pinfunction "CLK_38") (pintype "input"))
    )
    (net (code "7") (name "/MEM_CLK1") (class "Default")
      (node (ref "R53") (pin "2") (pinfunction "2_2") (pintype "passive"))
      (node (ref "U4") (pin "38") (pinfunction "CLK_38") (pintype "input"))
    )
    (net (code "8") (name "/MEM_CLK2") (class "Default")
      (node (ref "R56") (pin "2") (pinfunction "2_2") (pintype "passive"))
      (node (ref "U5") (pin "38") (pinfunction "CLK_38") (pintype "input"))
    )
    (net (code "9") (name "/MEM_CLK3") (class "Default")
      (node (ref "R58") (pin "2") (pinfunction "2_2") (pintype "passive"))
      (node (ref "U6") (pin "38") (pinfunction "CLK_38") (pintype "input"))
    )
    (net (code "10") (name "/MEM_CLK4") (class "Default")
      (node (ref "R60") (pin "2") (pinfunction "2_2") (pintype "passive"))
      (node (ref "U7") (pin "38") (pinfunction "CLK_38") (pintype "input"))
    )
    (net (code "11") (name "/MEM_CLK5") (class "Default")
      (node (ref "R61") (pin "2") (pinfunction "2_2") (pintype "passive"))
      (node (ref "U8") (pin "38") (pinfunction "CLK_38") (pintype "input"))
    )
    (net (code "12") (name "/MEM_CLK_N") (class "Default")
      (node (ref "IC7") (pin "2") (pinfunction "CLKINB_2") (pintype "passive"))
      (node (ref "R54") (pin "1") (pinfunction "1_1") (pintype "passive"))
    )
    (net (code "13") (name "/MEM_CLK_OUT") (class "Default")
      (node (ref "R50") (pin "1") (pinfunction "1_1") (pintype "passive"))
    )
    (net (code "14") (name "/MEM_CLK_P") (class "Default")
      (node (ref "IC7") (pin "1") (pinfunction "CLKIN_1") (pintype "passive"))
      (node (ref "R54") (pin "2") (pinfunction "2_2") (pintype "passive"))
    )
    (net (code "15") (name "/MEM_CS") (class "Default")
      (node (ref "U3") (pin "19") (pinfunction "CS#_19") (pintype "input"))
      (node (ref "U4") (pin "19") (pinfunction "CS#_19") (pintype "input"))
      (node (ref "U5") (pin "19") (pinfunction "CS#_19") (pintype "input"))
      (node (ref "U6") (pin "19") (pinfunction "CS#_19") (pintype "input"))
      (node (ref "U7") (pin "19") (pinfunction "CS#_19") (pintype "input"))
      (node (ref "U8") (pin "19") (pinfunction "CS#_19") (pintype "input"))
    )
    (net (code "16") (name "/MEM_DQ0") (class "Default")
      (node (ref "U3") (pin "2") (pinfunction "DQ0_2") (pintype "bidirectional"))
    )
    (net (code "17") (name "/MEM_DQ1") (class "Default")
      (node (ref "U3") (pin "4") (pinfunction "DQ1_4") (pintype "bidirectional"))
    )
    (net (code "18") (name "/MEM_DQ2") (class "Default")
      (node (ref "U3") (pin "5") (pinfunction "DQ2_5") (pintype "bidirectional"))
    )
    (net (code "19") (name "/MEM_DQ3") (class "Default")
      (node (ref "U3") (pin "7") (pinfunction "DQ3_7") (pintype "bidirectional"))
    )
    (net (code "20") (name "/MEM_DQ4") (class "Default")
      (node (ref "U3") (pin "8") (pinfunction "DQ4_8") (pintype "bidirectional"))
    )
    (net (code "21") (name "/MEM_DQ5") (class "Default")
      (node (ref "U3") (pin "10") (pinfunction "DQ5_10") (pintype "bidirectional"))
    )
    (net (code "22") (name "/MEM_DQ6") (class "Default")
      (node (ref "U3") (pin "11") (pinfunction "DQ6_11") (pintype "bidirectional"))
    )
    (net (code "23") (name "/MEM_DQ7") (class "Default")
      (node (ref "U3") (pin "13") (pinfunction "DQ7_13") (pintype "bidirectional"))
    )
    (net (code "24") (name "/MEM_DQ8") (class "Default")
      (node (ref "U3") (pin "42") (pinfunction "DQ8_42") (pintype "bidirectional"))
    )
    (net (code "25") (name "/MEM_DQ9") (class "Default")
      (node (ref "U3") (pin "44") (pinfunction "DQ9_44") (pintype "bidirectional"))
    )
    (net (code "26") (name "/MEM_DQ10") (class "Default")
      (node (ref "U3") (pin "45") (pinfunction "DQ10_45") (pintype "bidirectional"))
    )
    (net (code "27") (name "/MEM_DQ11") (class "Default")
      (node (ref "U3") (pin "47") (pinfunction "DQ11_47") (pintype "bidirectional"))
    )
    (net (code "28") (name "/MEM_DQ12") (class "Default")
      (node (ref "U3") (pin "48") (pinfunction "DQ12_48") (pintype "bidirectional"))
    )
    (net (code "29") (name "/MEM_DQ13") (class "Default")
      (node (ref "U3") (pin "50") (pinfunction "DQ13_50") (pintype "bidirectional"))
    )
    (net (code "30") (name "/MEM_DQ14") (class "Default")
      (node (ref "U3") (pin "51") (pinfunction "DQ14_51") (pintype "bidirectional"))
    )
    (net (code "31") (name "/MEM_DQ15") (class "Default")
      (node (ref "U3") (pin "53") (pinfunction "DQ15_53") (pintype "bidirectional"))
    )
    (net (code "32") (name "/MEM_DQ16") (class "Default")
      (node (ref "U4") (pin "2") (pinfunction "DQ0_2") (pintype "bidirectional"))
    )
    (net (code "33") (name "/MEM_DQ17") (class "Default")
      (node (ref "U4") (pin "4") (pinfunction "DQ1_4") (pintype "bidirectional"))
    )
    (net (code "34") (name "/MEM_DQ18") (class "Default")
      (node (ref "U4") (pin "5") (pinfunction "DQ2_5") (pintype "bidirectional"))
    )
    (net (code "35") (name "/MEM_DQ19") (class "Default")
      (node (ref "U4") (pin "7") (pinfunction "DQ3_7") (pintype "bidirectional"))
    )
    (net (code "36") (name "/MEM_DQ20") (class "Default")
      (node (ref "U4") (pin "8") (pinfunction "DQ4_8") (pintype "bidirectional"))
    )
    (net (code "37") (name "/MEM_DQ21") (class "Default")
      (node (ref "U4") (pin "10") (pinfunction "DQ5_10") (pintype "bidirectional"))
    )
    (net (code "38") (name "/MEM_DQ22") (class "Default")
      (node (ref "U4") (pin "11") (pinfunction "DQ6_11") (pintype "bidirectional"))
    )
    (net (code "39") (name "/MEM_DQ23") (class "Default")
      (node (ref "U4") (pin "13") (pinfunction "DQ7_13") (pintype "bidirectional"))
    )
    (net (code "40") (name "/MEM_DQ24") (class "Default")
      (node (ref "U4") (pin "42") (pinfunction "DQ8_42") (pintype "bidirectional"))
    )
    (net (code "41") (name "/MEM_DQ25") (class "Default")
      (node (ref "U4") (pin "44") (pinfunction "DQ9_44") (pintype "bidirectional"))
    )
    (net (code "42") (name "/MEM_DQ26") (class "Default")
      (node (ref "U4") (pin "45") (pinfunction "DQ10_45") (pintype "bidirectional"))
    )
    (net (code "43") (name "/MEM_DQ27") (class "Default")
      (node (ref "U4") (pin "47") (pinfunction "DQ11_47") (pintype "bidirectional"))
    )
    (net (code "44") (name "/MEM_DQ28") (class "Default")
      (node (ref "U4") (pin "48") (pinfunction "DQ12_48") (pintype "bidirectional"))
    )
    (net (code "45") (name "/MEM_DQ29") (class "Default")
      (node (ref "U4") (pin "50") (pinfunction "DQ13_50") (pintype "bidirectional"))
    )
    (net (code "46") (name "/MEM_DQ30") (class "Default")
      (node (ref "U4") (pin "51") (pinfunction "DQ14_51") (pintype "bidirectional"))
    )
    (net (code "47") (name "/MEM_DQ31") (class "Default")
      (node (ref "U4") (pin "53") (pinfunction "DQ15_53") (pintype "bidirectional"))
    )
    (net (code "48") (name "/MEM_DQ32") (class "Default")
      (node (ref "U5") (pin "2") (pinfunction "DQ0_2") (pintype "bidirectional"))
    )
    (net (code "49") (name "/MEM_DQ33") (class "Default")
      (node (ref "U5") (pin "4") (pinfunction "DQ1_4") (pintype "bidirectional"))
    )
    (net (code "50") (name "/MEM_DQ34") (class "Default")
      (node (ref "U5") (pin "5") (pinfunction "DQ2_5") (pintype "bidirectional"))
    )
    (net (code "51") (name "/MEM_DQ35") (class "Default")
      (node (ref "U5") (pin "7") (pinfunction "DQ3_7") (pintype "bidirectional"))
    )
    (net (code "52") (name "/MEM_DQ36") (class "Default")
      (node (ref "U5") (pin "8") (pinfunction "DQ4_8") (pintype "bidirectional"))
    )
    (net (code "53") (name "/MEM_DQ37") (class "Default")
      (node (ref "U5") (pin "10") (pinfunction "DQ5_10") (pintype "bidirectional"))
    )
    (net (code "54") (name "/MEM_DQ38") (class "Default")
      (node (ref "U5") (pin "11") (pinfunction "DQ6_11") (pintype "bidirectional"))
    )
    (net (code "55") (name "/MEM_DQ39") (class "Default")
      (node (ref "U5") (pin "13") (pinfunction "DQ7_13") (pintype "bidirectional"))
    )
    (net (code "56") (name "/MEM_DQ40") (class "Default")
      (node (ref "U5") (pin "42") (pinfunction "DQ8_42") (pintype "bidirectional"))
    )
    (net (code "57") (name "/MEM_DQ41") (class "Default")
      (node (ref "U5") (pin "44") (pinfunction "DQ9_44") (pintype "bidirectional"))
    )
    (net (code "58") (name "/MEM_DQ42") (class "Default")
      (node (ref "U5") (pin "45") (pinfunction "DQ10_45") (pintype "bidirectional"))
    )
    (net (code "59") (name "/MEM_DQ43") (class "Default")
      (node (ref "U5") (pin "47") (pinfunction "DQ11_47") (pintype "bidirectional"))
    )
    (net (code "60") (name "/MEM_DQ44") (class "Default")
      (node (ref "U5") (pin "48") (pinfunction "DQ12_48") (pintype "bidirectional"))
    )
    (net (code "61") (name "/MEM_DQ45") (class "Default")
      (node (ref "U5") (pin "50") (pinfunction "DQ13_50") (pintype "bidirectional"))
    )
    (net (code "62") (name "/MEM_DQ46") (class "Default")
      (node (ref "U5") (pin "51") (pinfunction "DQ14_51") (pintype "bidirectional"))
    )
    (net (code "63") (name "/MEM_DQ47") (class "Default")
      (node (ref "U5") (pin "53") (pinfunction "DQ15_53") (pintype "bidirectional"))
    )
    (net (code "64") (name "/MEM_DQ48") (class "Default")
      (node (ref "U6") (pin "2") (pinfunction "DQ0_2") (pintype "bidirectional"))
    )
    (net (code "65") (name "/MEM_DQ49") (class "Default")
      (node (ref "U6") (pin "4") (pinfunction "DQ1_4") (pintype "bidirectional"))
    )
    (net (code "66") (name "/MEM_DQ50") (class "Default")
      (node (ref "U6") (pin "5") (pinfunction "DQ2_5") (pintype "bidirectional"))
    )
    (net (code "67") (name "/MEM_DQ51") (class "Default")
      (node (ref "U6") (pin "7") (pinfunction "DQ3_7") (pintype "bidirectional"))
    )
    (net (code "68") (name "/MEM_DQ52") (class "Default")
      (node (ref "U6") (pin "8") (pinfunction "DQ4_8") (pintype "bidirectional"))
    )
    (net (code "69") (name "/MEM_DQ53") (class "Default")
      (node (ref "U6") (pin "10") (pinfunction "DQ5_10") (pintype "bidirectional"))
    )
    (net (code "70") (name "/MEM_DQ54") (class "Default")
      (node (ref "U6") (pin "11") (pinfunction "DQ6_11") (pintype "bidirectional"))
    )
    (net (code "71") (name "/MEM_DQ55") (class "Default")
      (node (ref "U6") (pin "13") (pinfunction "DQ7_13") (pintype "bidirectional"))
    )
    (net (code "72") (name "/MEM_DQ56") (class "Default")
      (node (ref "U6") (pin "42") (pinfunction "DQ8_42") (pintype "bidirectional"))
    )
    (net (code "73") (name "/MEM_DQ57") (class "Default")
      (node (ref "U6") (pin "44") (pinfunction "DQ9_44") (pintype "bidirectional"))
    )
    (net (code "74") (name "/MEM_DQ58") (class "Default")
      (node (ref "U6") (pin "45") (pinfunction "DQ10_45") (pintype "bidirectional"))
    )
    (net (code "75") (name "/MEM_DQ59") (class "Default")
      (node (ref "U6") (pin "47") (pinfunction "DQ11_47") (pintype "bidirectional"))
    )
    (net (code "76") (name "/MEM_DQ60") (class "Default")
      (node (ref "U6") (pin "48") (pinfunction "DQ12_48") (pintype "bidirectional"))
    )
    (net (code "77") (name "/MEM_DQ61") (class "Default")
      (node (ref "U6") (pin "50") (pinfunction "DQ13_50") (pintype "bidirectional"))
    )
    (net (code "78") (name "/MEM_DQ62") (class "Default")
      (node (ref "U6") (pin "51") (pinfunction "DQ14_51") (pintype "bidirectional"))
    )
    (net (code "79") (name "/MEM_DQ63") (class "Default")
      (node (ref "U6") (pin "53") (pinfunction "DQ15_53") (pintype "bidirectional"))
    )
    (net (code "80") (name "/MEM_DQ64") (class "Default")
      (node (ref "U7") (pin "2") (pinfunction "DQ0_2") (pintype "bidirectional"))
    )
    (net (code "81") (name "/MEM_DQ65") (class "Default")
      (node (ref "U7") (pin "4") (pinfunction "DQ1_4") (pintype "bidirectional"))
    )
    (net (code "82") (name "/MEM_DQ66") (class "Default")
      (node (ref "U7") (pin "5") (pinfunction "DQ2_5") (pintype "bidirectional"))
    )
    (net (code "83") (name "/MEM_DQ67") (class "Default")
      (node (ref "U7") (pin "7") (pinfunction "DQ3_7") (pintype "bidirectional"))
    )
    (net (code "84") (name "/MEM_DQ68") (class "Default")
      (node (ref "U7") (pin "8") (pinfunction "DQ4_8") (pintype "bidirectional"))
    )
    (net (code "85") (name "/MEM_DQ69") (class "Default")
      (node (ref "U7") (pin "10") (pinfunction "DQ5_10") (pintype "bidirectional"))
    )
    (net (code "86") (name "/MEM_DQ70") (class "Default")
      (node (ref "U7") (pin "11") (pinfunction "DQ6_11") (pintype "bidirectional"))
    )
    (net (code "87") (name "/MEM_DQ71") (class "Default")
      (node (ref "U7") (pin "13") (pinfunction "DQ7_13") (pintype "bidirectional"))
    )
    (net (code "88") (name "/MEM_DQ72") (class "Default")
      (node (ref "U7") (pin "42") (pinfunction "DQ8_42") (pintype "bidirectional"))
    )
    (net (code "89") (name "/MEM_DQ73") (class "Default")
      (node (ref "U7") (pin "44") (pinfunction "DQ9_44") (pintype "bidirectional"))
    )
    (net (code "90") (name "/MEM_DQ74") (class "Default")
      (node (ref "U7") (pin "45") (pinfunction "DQ10_45") (pintype "bidirectional"))
    )
    (net (code "91") (name "/MEM_DQ75") (class "Default")
      (node (ref "U7") (pin "47") (pinfunction "DQ11_47") (pintype "bidirectional"))
    )
    (net (code "92") (name "/MEM_DQ76") (class "Default")
      (node (ref "U7") (pin "48") (pinfunction "DQ12_48") (pintype "bidirectional"))
    )
    (net (code "93") (name "/MEM_DQ77") (class "Default")
      (node (ref "U7") (pin "50") (pinfunction "DQ13_50") (pintype "bidirectional"))
    )
    (net (code "94") (name "/MEM_DQ78") (class "Default")
      (node (ref "U7") (pin "51") (pinfunction "DQ14_51") (pintype "bidirectional"))
    )
    (net (code "95") (name "/MEM_DQ79") (class "Default")
      (node (ref "U7") (pin "53") (pinfunction "DQ15_53") (pintype "bidirectional"))
    )
    (net (code "96") (name "/MEM_DQ80") (class "Default")
      (node (ref "U8") (pin "2") (pinfunction "DQ0_2") (pintype "bidirectional"))
    )
    (net (code "97") (name "/MEM_DQ81") (class "Default")
      (node (ref "U8") (pin "4") (pinfunction "DQ1_4") (pintype "bidirectional"))
    )
    (net (code "98") (name "/MEM_DQ82") (class "Default")
      (node (ref "U8") (pin "5") (pinfunction "DQ2_5") (pintype "bidirectional"))
    )
    (net (code "99") (name "/MEM_DQ83") (class "Default")
      (node (ref "U8") (pin "7") (pinfunction "DQ3_7") (pintype "bidirectional"))
    )
    (net (code "100") (name "/MEM_DQ84") (class "Default")
      (node (ref "U8") (pin "8") (pinfunction "DQ4_8") (pintype "bidirectional"))
    )
    (net (code "101") (name "/MEM_DQ85") (class "Default")
      (node (ref "U8") (pin "10") (pinfunction "DQ5_10") (pintype "bidirectional"))
    )
    (net (code "102") (name "/MEM_DQ86") (class "Default")
      (node (ref "U8") (pin "11") (pinfunction "DQ6_11") (pintype "bidirectional"))
    )
    (net (code "103") (name "/MEM_DQ87") (class "Default")
      (node (ref "U8") (pin "13") (pinfunction "DQ7_13") (pintype "bidirectional"))
    )
    (net (code "104") (name "/MEM_DQ88") (class "Default")
      (node (ref "U8") (pin "42") (pinfunction "DQ8_42") (pintype "bidirectional"))
    )
    (net (code "105") (name "/MEM_DQ89") (class "Default")
      (node (ref "U8") (pin "44") (pinfunction "DQ9_44") (pintype "bidirectional"))
    )
    (net (code "106") (name "/MEM_DQ90") (class "Default")
      (node (ref "U8") (pin "45") (pinfunction "DQ10_45") (pintype "bidirectional"))
    )
    (net (code "107") (name "/MEM_DQ91") (class "Default")
      (node (ref "U8") (pin "47") (pinfunction "DQ11_47") (pintype "bidirectional"))
    )
    (net (code "108") (name "/MEM_DQ92") (class "Default")
      (node (ref "U8") (pin "48") (pinfunction "DQ12_48") (pintype "bidirectional"))
    )
    (net (code "109") (name "/MEM_DQ93") (class "Default")
      (node (ref "U8") (pin "50") (pinfunction "DQ13_50") (pintype "bidirectional"))
    )
    (net (code "110") (name "/MEM_DQ94") (class "Default")
      (node (ref "U8") (pin "51") (pinfunction "DQ14_51") (pintype "bidirectional"))
    )
    (net (code "111") (name "/MEM_DQ95") (class "Default")
      (node (ref "U8") (pin "53") (pinfunction "DQ15_53") (pintype "bidirectional"))
    )
    (net (code "112") (name "/MEM_DQM0") (class "Default")
      (node (ref "U3") (pin "15") (pinfunction "DQML_15") (pintype "input"))
    )
    (net (code "113") (name "/MEM_DQM1") (class "Default")
      (node (ref "U3") (pin "39") (pinfunction "DQMH_39") (pintype "input"))
    )
    (net (code "114") (name "/MEM_DQM2") (class "Default")
      (node (ref "U4") (pin "15") (pinfunction "DQML_15") (pintype "input"))
    )
    (net (code "115") (name "/MEM_DQM3") (class "Default")
      (node (ref "U4") (pin "39") (pinfunction "DQMH_39") (pintype "input"))
    )
    (net (code "116") (name "/MEM_DQM4") (class "Default")
      (node (ref "U5") (pin "15") (pinfunction "DQML_15") (pintype "input"))
    )
    (net (code "117") (name "/MEM_DQM5") (class "Default")
      (node (ref "U5") (pin "39") (pinfunction "DQMH_39") (pintype "input"))
    )
    (net (code "118") (name "/MEM_DQM6") (class "Default")
      (node (ref "U6") (pin "15") (pinfunction "DQML_15") (pintype "input"))
    )
    (net (code "119") (name "/MEM_DQM7") (class "Default")
      (node (ref "U6") (pin "39") (pinfunction "DQMH_39") (pintype "input"))
    )
    (net (code "120") (name "/MEM_DQM8") (class "Default")
      (node (ref "U7") (pin "15") (pinfunction "DQML_15") (pintype "input"))
    )
    (net (code "121") (name "/MEM_DQM9") (class "Default")
      (node (ref "U7") (pin "39") (pinfunction "DQMH_39") (pintype "input"))
    )
    (net (code "122") (name "/MEM_DQM10") (class "Default")
      (node (ref "U8") (pin "15") (pinfunction "DQML_15") (pintype "input"))
    )
    (net (code "123") (name "/MEM_DQM11") (class "Default")
      (node (ref "U8") (pin "39") (pinfunction "DQMH_39") (pintype "input"))
    )
    (net (code "126") (name "/MEM_RAS") (class "Default")
      (node (ref "U3") (pin "18") (pinfunction "RAS#_18") (pintype "input"))
      (node (ref "U4") (pin "18") (pinfunction "RAS#_18") (pintype "input"))
      (node (ref "U5") (pin "18") (pinfunction "RAS#_18") (pintype "input"))
      (node (ref "U6") (pin "18") (pinfunction "RAS#_18") (pintype "input"))
      (node (ref "U7") (pin "18") (pinfunction "RAS#_18") (pintype "input"))
      (node (ref "U8") (pin "18") (pinfunction "RAS#_18") (pintype "input"))
    )
    (net (code "127") (name "/MEM_WE") (class "Default")
      (node (ref "U3") (pin "16") (pinfunction "WE#_16") (pintype "input"))
      (node (ref "U4") (pin "16") (pinfunction "WE#_16") (pintype "input"))
      (node (ref "U5") (pin "16") (pinfunction "WE#_16") (pintype "input"))
      (node (ref "U6") (pin "16") (pinfunction "WE#_16") (pintype "input"))
      (node (ref "U7") (pin "16") (pinfunction "WE#_16") (pintype "input"))
      (node (ref "U8") (pin "16") (pinfunction "WE#_16") (pintype "input"))
    )
    (net (code "128") (name "/RAM_A0") (class "Default")
      (node (ref "U3") (pin "23") (pinfunction "A0_23") (pintype "input"))
      (node (ref "U4") (pin "23") (pinfunction "A0_23") (pintype "input"))
      (node (ref "U5") (pin "23") (pinfunction "A0_23") (pintype "input"))
      (node (ref "U6") (pin "23") (pinfunction "A0_23") (pintype "input"))
      (node (ref "U7") (pin "23") (pinfunction "A0_23") (pintype "input"))
      (node (ref "U8") (pin "23") (pinfunction "A0_23") (pintype "input"))
    )
    (net (code "129") (name "/RAM_A1") (class "Default")
      (node (ref "U3") (pin "24") (pinfunction "A1_24") (pintype "input"))
      (node (ref "U4") (pin "24") (pinfunction "A1_24") (pintype "input"))
      (node (ref "U5") (pin "24") (pinfunction "A1_24") (pintype "input"))
      (node (ref "U6") (pin "24") (pinfunction "A1_24") (pintype "input"))
      (node (ref "U7") (pin "24") (pinfunction "A1_24") (pintype "input"))
      (node (ref "U8") (pin "24") (pinfunction "A1_24") (pintype "input"))
    )
    (net (code "130") (name "/RAM_A2") (class "Default")
      (node (ref "U3") (pin "25") (pinfunction "A2_25") (pintype "input"))
      (node (ref "U4") (pin "25") (pinfunction "A2_25") (pintype "input"))
      (node (ref "U5") (pin "25") (pinfunction "A2_25") (pintype "input"))
      (node (ref "U6") (pin "25") (pinfunction "A2_25") (pintype "input"))
      (node (ref "U7") (pin "25") (pinfunction "A2_25") (pintype "input"))
      (node (ref "U8") (pin "25") (pinfunction "A2_25") (pintype "input"))
    )
    (net (code "131") (name "/RAM_A3") (class "Default")
      (node (ref "U3") (pin "26") (pinfunction "A3_26") (pintype "input"))
      (node (ref "U4") (pin "26") (pinfunction "A3_26") (pintype "input"))
      (node (ref "U5") (pin "26") (pinfunction "A3_26") (pintype "input"))
      (node (ref "U6") (pin "26") (pinfunction "A3_26") (pintype "input"))
      (node (ref "U7") (pin "26") (pinfunction "A3_26") (pintype "input"))
      (node (ref "U8") (pin "26") (pinfunction "A3_26") (pintype "input"))
    )
    (net (code "132") (name "/RAM_A4") (class "Default")
      (node (ref "U3") (pin "29") (pinfunction "A4_29") (pintype "input"))
      (node (ref "U4") (pin "29") (pinfunction "A4_29") (pintype "input"))
      (node (ref "U5") (pin "29") (pinfunction "A4_29") (pintype "input"))
      (node (ref "U6") (pin "29") (pinfunction "A4_29") (pintype "input"))
      (node (ref "U7") (pin "29") (pinfunction "A4_29") (pintype "input"))
      (node (ref "U8") (pin "29") (pinfunction "A4_29") (pintype "input"))
    )
    (net (code "133") (name "/RAM_A5") (class "Default")
      (node (ref "U3") (pin "30") (pinfunction "A5_30") (pintype "input"))
      (node (ref "U4") (pin "30") (pinfunction "A5_30") (pintype "input"))
      (node (ref "U5") (pin "30") (pinfunction "A5_30") (pintype "input"))
      (node (ref "U6") (pin "30") (pinfunction "A5_30") (pintype "input"))
      (node (ref "U7") (pin "30") (pinfunction "A5_30") (pintype "input"))
      (node (ref "U8") (pin "30") (pinfunction "A5_30") (pintype "input"))
    )
    (net (code "134") (name "/RAM_A6") (class "Default")
      (node (ref "U3") (pin "31") (pinfunction "A6_31") (pintype "input"))
      (node (ref "U4") (pin "31") (pinfunction "A6_31") (pintype "input"))
      (node (ref "U5") (pin "31") (pinfunction "A6_31") (pintype "input"))
      (node (ref "U6") (pin "31") (pinfunction "A6_31") (pintype "input"))
      (node (ref "U7") (pin "31") (pinfunction "A6_31") (pintype "input"))
      (node (ref "U8") (pin "31") (pinfunction "A6_31") (pintype "input"))
    )
    (net (code "135") (name "/RAM_A7") (class "Default")
      (node (ref "U3") (pin "32") (pinfunction "A7_32") (pintype "input"))
      (node (ref "U4") (pin "32") (pinfunction "A7_32") (pintype "input"))
      (node (ref "U5") (pin "32") (pinfunction "A7_32") (pintype "input"))
      (node (ref "U6") (pin "32") (pinfunction "A7_32") (pintype "input"))
      (node (ref "U7") (pin "32") (pinfunction "A7_32") (pintype "input"))
      (node (ref "U8") (pin "32") (pinfunction "A7_32") (pintype "input"))
    )
    (net (code "136") (name "/RAM_A8") (class "Default")
      (node (ref "U3") (pin "33") (pinfunction "A8_33") (pintype "input"))
      (node (ref "U4") (pin "33") (pinfunction "A8_33") (pintype "input"))
      (node (ref "U5") (pin "33") (pinfunction "A8_33") (pintype "input"))
      (node (ref "U6") (pin "33") (pinfunction "A8_33") (pintype "input"))
      (node (ref "U7") (pin "33") (pinfunction "A8_33") (pintype "input"))
      (node (ref "U8") (pin "33") (pinfunction "A8_33") (pintype "input"))
    )
    (net (code "137") (name "/RAM_A9") (class "Default")
      (node (ref "U3") (pin "34") (pinfunction "A9_34") (pintype "input"))
      (node (ref "U4") (pin "34") (pinfunction "A9_34") (pintype "input"))
      (node (ref "U5") (pin "34") (pinfunction "A9_34") (pintype "input"))
      (node (ref "U6") (pin "34") (pinfunction "A9_34") (pintype "input"))
      (node (ref "U7") (pin "34") (pinfunction "A9_34") (pintype "input"))
      (node (ref "U8") (pin "34") (pinfunction "A9_34") (pintype "input"))
    )
    (net (code "138") (name "/RAM_A10") (class "Default")
      (node (ref "U3") (pin "22") (pinfunction "A10_22") (pintype "input"))
      (node (ref "U4") (pin "22") (pinfunction "A10_22") (pintype "input"))
      (node (ref "U5") (pin "22") (pinfunction "A10_22") (pintype "input"))
      (node (ref "U6") (pin "22") (pinfunction "A10_22") (pintype "input"))
      (node (ref "U7") (pin "22") (pinfunction "A10_22") (pintype "input"))
      (node (ref "U8") (pin "22") (pinfunction "A10_22") (pintype "input"))
    )
    (net (code "139") (name "/RAM_A11") (class "Default")
      (node (ref "U3") (pin "35") (pinfunction "A11_35") (pintype "input"))
      (node (ref "U4") (pin "35") (pinfunction "A11_35") (pintype "input"))
      (node (ref "U5") (pin "35") (pinfunction "A11_35") (pintype "input"))
      (node (ref "U6") (pin "35") (pinfunction "A11_35") (pintype "input"))
      (node (ref "U7") (pin "35") (pinfunction "A11_35") (pintype "input"))
      (node (ref "U8") (pin "35") (pinfunction "A11_35") (pintype "input"))
    )
    (net (code "140") (name "/RAM_A12") (class "Default")
      (node (ref "U3") (pin "36") (pinfunction "A12_36") (pintype "input"))
      (node (ref "U4") (pin "36") (pinfunction "A12_36") (pintype "input"))
      (node (ref "U5") (pin "36") (pinfunction "A12_36") (pintype "input"))
      (node (ref "U6") (pin "36") (pinfunction "A12_36") (pintype "input"))
      (node (ref "U7") (pin "36") (pinfunction "A12_36") (pintype "input"))
      (node (ref "U8") (pin "36") (pinfunction "A12_36") (pintype "input"))
    )
    (net (code "144") (name "GND") (class "Default")
      (node (ref "C116") (pin "1") (pinfunction "1_1") (pintype "passive"))
      (node (ref "C117") (pin "2") (pinfunction "2_2") (pintype "passive"))
      (node (ref "C118") (pin "2") (pinfunction "2_2") (pintype "passive"))
      (node (ref "C119") (pin "2") (pinfunction "2_2") (pintype "passive"))
      (node (ref "C120") (pin "2") (pinfunction "2_2") (pintype "passive"))
      (node (ref "C121") (pin "2") (pinfunction "2_2") (pintype "passive"))
      (node (ref "C122") (pin "2") (pinfunction "2_2") (pintype "passive"))
      (node (ref "C123") (pin "1") (pinfunction "1_1") (pintype "passive"))
      (node (ref "C124") (pin "2") (pinfunction "2_2") (pintype "passive"))
      (node (ref "C125") (pin "2") (pinfunction "2_2") (pintype "passive"))
      (node (ref "C126") (pin "2") (pinfunction "2_2") (pintype "passive"))
      (node (ref "C127") (pin "2") (pinfunction "2_2") (pintype "passive"))
      (node (ref "C128") (pin "2") (pinfunction "2_2") (pintype "passive"))
      (node (ref "C129") (pin "2") (pinfunction "2_2") (pintype "passive"))
      (node (ref "C131") (pin "1") (pinfunction "1_1") (pintype "passive"))
      (node (ref "C132") (pin "2") (pinfunction "2_2") (pintype "passive"))
      (node (ref "C133") (pin "2") (pinfunction "2_2") (pintype "passive"))
      (node (ref "C134") (pin "2") (pinfunction "2_2") (pintype "passive"))
      (node (ref "C135") (pin "2") (pinfunction "2_2") (pintype "passive"))
      (node (ref "C136") (pin "2") (pinfunction "2_2") (pintype "passive"))
      (node (ref "C137") (pin "2") (pinfunction "2_2") (pintype "passive"))
      (node (ref "C138") (pin "1") (pinfunction "1_1") (pintype "passive"))
      (node (ref "C139") (pin "2") (pinfunction "2_2") (pintype "passive"))
      (node (ref "C140") (pin "2") (pinfunction "2_2") (pintype "passive"))
      (node (ref "C141") (pin "2") (pinfunction "2_2") (pintype "passive"))
      (node (ref "C142") (pin "2") (pinfunction "2_2") (pintype "passive"))
      (node (ref "C143") (pin "2") (pinfunction "2_2") (pintype "passive"))
      (node (ref "C144") (pin "2") (pinfunction "2_2") (pintype "passive"))
      (node (ref "C145") (pin "1") (pinfunction "1_1") (pintype "passive"))
      (node (ref "C146") (pin "2") (pinfunction "2_2") (pintype "passive"))
      (node (ref "C147") (pin "1") (pinfunction "1_1") (pintype "passive"))
      (node (ref "C148") (pin "2") (pinfunction "2_2") (pintype "passive"))
      (node (ref "C149") (pin "2") (pinfunction "2_2") (pintype "passive"))
      (node (ref "C150") (pin "2") (pinfunction "2_2") (pintype "passive"))
      (node (ref "C151") (pin "2") (pinfunction "2_2") (pintype "passive"))
      (node (ref "C152") (pin "2") (pinfunction "2_2") (pintype "passive"))
      (node (ref "C153") (pin "2") (pinfunction "2_2") (pintype "passive"))
      (node (ref "C154") (pin "1") (pinfunction "1_1") (pintype "passive"))
      (node (ref "C155") (pin "2") (pinfunction "2_2") (pintype "passive"))
      (node (ref "C156") (pin "2") (pinfunction "2_2") (pintype "passive"))
      (node (ref "C157") (pin "2") (pinfunction "2_2") (pintype "passive"))
      (node (ref "C158") (pin "2") (pinfunction "2_2") (pintype "passive"))
      (node (ref "C159") (pin "2") (pinfunction "2_2") (pintype "passive"))
      (node (ref "C160") (pin "2") (pinfunction "2_2") (pintype "passive"))
      (node (ref "C161") (pin "1") (pinfunction "1_1") (pintype "passive"))
      (node (ref "C162") (pin "2") (pinfunction "2_2") (pintype "passive"))
      (node (ref "C163") (pin "2") (pinfunction "2_2") (pintype "passive"))
      (node (ref "C164") (pin "2") (pinfunction "2_2") (pintype "passive"))
      (node (ref "C165") (pin "2") (pinfunction "2_2") (pintype "passive"))
      (node (ref "C166") (pin "2") (pinfunction "2_2") (pintype "passive"))
      (node (ref "C167") (pin "2") (pinfunction "2_2") (pintype "passive"))
      (node (ref "IC7") (pin "25") (pinfunction "PAD_GND_25") (pintype "passive"))
      (node (ref "R51") (pin "1") (pinfunction "1_1") (pintype "passive"))
      (node (ref "R57") (pin "1") (pinfunction "1_1") (pintype "passive"))
      (node (ref "U3") (pin "12") (pinfunction "VSSQ_12") (pintype "power_in"))
      (node (ref "U3") (pin "28") (pinfunction "VSS_28") (pintype "power_in"))
      (node (ref "U3") (pin "41") (pinfunction "VSS_41") (pintype "power_in"))
      (node (ref "U3") (pin "46") (pinfunction "VSSQ_46") (pintype "power_in"))
      (node (ref "U3") (pin "52") (pinfunction "VSSQ_52") (pintype "power_in"))
      (node (ref "U3") (pin "54") (pinfunction "VSS_54") (pintype "power_in"))
      (node (ref "U3") (pin "6") (pinfunction "VSSQ_6") (pintype "power_in"))
      (node (ref "U4") (pin "12") (pinfunction "VSSQ_12") (pintype "power_in"))
      (node (ref "U4") (pin "28") (pinfunction "VSS_28") (pintype "power_in"))
      (node (ref "U4") (pin "41") (pinfunction "VSS_41") (pintype "power_in"))
      (node (ref "U4") (pin "46") (pinfunction "VSSQ_46") (pintype "power_in"))
      (node (ref "U4") (pin "52") (pinfunction "VSSQ_52") (pintype "power_in"))
      (node (ref "U4") (pin "54") (pinfunction "VSS_54") (pintype "power_in"))
      (node (ref "U4") (pin "6") (pinfunction "VSSQ_6") (pintype "power_in"))
      (node (ref "U5") (pin "12") (pinfunction "VSSQ_12") (pintype "power_in"))
      (node (ref "U5") (pin "28") (pinfunction "VSS_28") (pintype "power_in"))
      (node (ref "U5") (pin "41") (pinfunction "VSS_41") (pintype "power_in"))
      (node (ref "U5") (pin "46") (pinfunction "VSSQ_46") (pintype "power_in"))
      (node (ref "U5") (pin "52") (pinfunction "VSSQ_52") (pintype "power_in"))
      (node (ref "U5") (pin "54") (pinfunction "VSS_54") (pintype "power_in"))
      (node (ref "U5") (pin "6") (pinfunction "VSSQ_6") (pintype "power_in"))
      (node (ref "U6") (pin "12") (pinfunction "VSSQ_12") (pintype "power_in"))
      (node (ref "U6") (pin "28") (pinfunction "VSS_28") (pintype "power_in"))
      (node (ref "U6") (pin "41") (pinfunction "VSS_41") (pintype "power_in"))
      (node (ref "U6") (pin "46") (pinfunction "VSSQ_46") (pintype "power_in"))
      (node (ref "U6") (pin "52") (pinfunction "VSSQ_52") (pintype "power_in"))
      (node (ref "U6") (pin "54") (pinfunction "VSS_54") (pintype "power_in"))
      (node (ref "U6") (pin "6") (pinfunction "VSSQ_6") (pintype "power_in"))
      (node (ref "U7") (pin "12") (pinfunction "VSSQ_12") (pintype "power_in"))
      (node (ref "U7") (pin "28") (pinfunction "VSS_28") (pintype "power_in"))
      (node (ref "U7") (pin "41") (pinfunction "VSS_41") (pintype "power_in"))
      (node (ref "U7") (pin "46") (pinfunction "VSSQ_46") (pintype "power_in"))
      (node (ref "U7") (pin "52") (pinfunction "VSSQ_52") (pintype "power_in"))
      (node (ref "U7") (pin "54") (pinfunction "VSS_54") (pintype "power_in"))
      (node (ref "U7") (pin "6") (pinfunction "VSSQ_6") (pintype "power_in"))
      (node (ref "U8") (pin "12") (pinfunction "VSSQ_12") (pintype "power_in"))
      (node (ref "U8") (pin "28") (pinfunction "VSS_28") (pintype "power_in"))
      (node (ref "U8") (pin "41") (pinfunction "VSS_41") (pintype "power_in"))
      (node (ref "U8") (pin "46") (pinfunction "VSSQ_46") (pintype "power_in"))
      (node (ref "U8") (pin "52") (pinfunction "VSSQ_52") (pintype "power_in"))
      (node (ref "U8") (pin "54") (pinfunction "VSS_54") (pintype "power_in"))
      (node (ref "U8") (pin "6") (pinfunction "VSSQ_6") (pintype "power_in"))
    )
    (net (code "145") (name "Net-(C130-Pad1)") (class "Default")
      (node (ref "C130") (pin "1") (pinfunction "1_1") (pintype "passive"))
      (node (ref "R50") (pin "2") (pinfunction "2_2") (pintype "passive"))
      (node (ref "R51") (pin "2") (pinfunction "2_2") (pintype "passive"))
    )
    (net (code "146") (name "Net-(IC7-CLKSEL)") (class "Default")
      (node (ref "IC7") (pin "6") (pinfunction "CLKSEL_6") (pintype "passive"))
      (node (ref "R55") (pin "2") (pinfunction "2_2") (pintype "passive"))
    )
    (net (code "147") (name "Net-(IC7-OUT0_SEL_I2C)") (class "Default")
      (node (ref "IC7") (pin "24") (pinfunction "OUT0_SEL_I2C_24") (pintype "passive"))
      (node (ref "R62") (pin "1") (pinfunction "1_1") (pintype "passive"))
    )
    (net (code "148") (name "Net-(IC7-OUT1)") (class "Default")
      (node (ref "IC7") (pin "20") (pinfunction "OUT1_20") (pintype "passive"))
      (node (ref "R52") (pin "1") (pinfunction "1_1") (pintype "passive"))
    )
    (net (code "149") (name "Net-(IC7-OUT1B)") (class "Default")
      (node (ref "IC7") (pin "19") (pinfunction "OUT1B_19") (pintype "passive"))
      (node (ref "R53") (pin "1") (pinfunction "1_1") (pintype "passive"))
    )
    (net (code "150") (name "Net-(IC7-OUT2)") (class "Default")
      (node (ref "IC7") (pin "17") (pinfunction "OUT2_17") (pintype "passive"))
      (node (ref "R56") (pin "1") (pinfunction "1_1") (pintype "passive"))
    )
    (net (code "151") (name "Net-(IC7-OUT2B)") (class "Default")
      (node (ref "IC7") (pin "16") (pinfunction "OUT2B_16") (pintype "passive"))
      (node (ref "R58") (pin "1") (pinfunction "1_1") (pintype "passive"))
    )
    (net (code "152") (name "Net-(IC7-OUT3)") (class "Default")
      (node (ref "IC7") (pin "14") (pinfunction "OUT3_14") (pintype "passive"))
      (node (ref "R60") (pin "1") (pinfunction "1_1") (pintype "passive"))
    )
    (net (code "153") (name "Net-(IC7-OUT3B)") (class "Default")
      (node (ref "IC7") (pin "13") (pinfunction "OUT3B_13") (pintype "passive"))
      (node (ref "R61") (pin "1") (pinfunction "1_1") (pintype "passive"))
    )
    (net (code "154") (name "Net-(IC7-SD{slash}OE)") (class "Default")
      (node (ref "IC7") (pin "7") (pinfunction "SD/OE_7") (pintype "passive"))
      (node (ref "R57") (pin "2") (pinfunction "2_2") (pintype "passive"))
    )
    (net (code "155") (name "Net-(IC7-VDDA)") (class "Default")
      (node (ref "C145") (pin "2") (pinfunction "2_2") (pintype "passive"))
      (node (ref "C146") (pin "1") (pinfunction "1_1") (pintype "passive"))
      (node (ref "IC7") (pin "5") (pinfunction "VDDA_5") (pintype "passive"))
      (node (ref "R59") (pin "2") (pinfunction "2_2") (pintype "passive"))
    )
    (net (code "156") (name "Net-(IC7-XIN{slash}REF)") (class "Default")
      (node (ref "C130") (pin "2") (pinfunction "2_2") (pintype "passive"))
      (node (ref "IC7") (pin "4") (pinfunction "XIN/REF_4") (pintype "passive"))
    )
    (net (code "157") (name "P3V3") (class "Default")
      (node (ref "C116") (pin "2") (pinfunction "2_2") (pintype "passive"))
      (node (ref "C117") (pin "1") (pinfunction "1_1") (pintype "passive"))
      (node (ref "C118") (pin "1") (pinfunction "1_1") (pintype "passive"))
      (node (ref "C119") (pin "1") (pinfunction "1_1") (pintype "passive"))
      (node (ref "C120") (pin "1") (pinfunction "1_1") (pintype "passive"))
      (node (ref "C121") (pin "1") (pinfunction "1_1") (pintype "passive"))
      (node (ref "C122") (pin "1") (pinfunction "1_1") (pintype "passive"))
      (node (ref "C123") (pin "2") (pinfunction "2_2") (pintype "passive"))
      (node (ref "C124") (pin "1") (pinfunction "1_1") (pintype "passive"))
      (node (ref "C125") (pin "1") (pinfunction "1_1") (pintype "passive"))
      (node (ref "C126") (pin "1") (pinfunction "1_1") (pintype "passive"))
      (node (ref "C127") (pin "1") (pinfunction "1_1") (pintype "passive"))
      (node (ref "C128") (pin "1") (pinfunction "1_1") (pintype "passive"))
      (node (ref "C129") (pin "1") (pinfunction "1_1") (pintype "passive"))
      (node (ref "C131") (pin "2") (pinfunction "2_2") (pintype "passive"))
      (node (ref "C132") (pin "1") (pinfunction "1_1") (pintype "passive"))
      (node (ref "C133") (pin "1") (pinfunction "1_1") (pintype "passive"))
      (node (ref "C134") (pin "1") (pinfunction "1_1") (pintype "passive"))
      (node (ref "C135") (pin "1") (pinfunction "1_1") (pintype "passive"))
      (node (ref "C136") (pin "1") (pinfunction "1_1") (pintype "passive"))
      (node (ref "C137") (pin "1") (pinfunction "1_1") (pintype "passive"))
      (node (ref "C138") (pin "2") (pinfunction "2_2") (pintype "passive"))
      (node (ref "C139") (pin "1") (pinfunction "1_1") (pintype "passive"))
      (node (ref "C140") (pin "1") (pinfunction "1_1") (pintype "passive"))
      (node (ref "C141") (pin "1") (pinfunction "1_1") (pintype "passive"))
      (node (ref "C142") (pin "1") (pinfunction "1_1") (pintype "passive"))
      (node (ref "C143") (pin "1") (pinfunction "1_1") (pintype "passive"))
      (node (ref "C144") (pin "1") (pinfunction "1_1") (pintype "passive"))
      (node (ref "C147") (pin "2") (pinfunction "2_2") (pintype "passive"))
      (node (ref "C148") (pin "1") (pinfunction "1_1") (pintype "passive"))
      (node (ref "C149") (pin "1") (pinfunction "1_1") (pintype "passive"))
      (node (ref "C150") (pin "1") (pinfunction "1_1") (pintype "passive"))
      (node (ref "C151") (pin "1") (pinfunction "1_1") (pintype "passive"))
      (node (ref "C152") (pin "1") (pinfunction "1_1") (pintype "passive"))
      (node (ref "C153") (pin "1") (pinfunction "1_1") (pintype "passive"))
      (node (ref "C154") (pin "2") (pinfunction "2_2") (pintype "passive"))
      (node (ref "C155") (pin "1") (pinfunction "1_1") (pintype "passive"))
      (node (ref "C156") (pin "1") (pinfunction "1_1") (pintype "passive"))
      (node (ref "C157") (pin "1") (pinfunction "1_1") (pintype "passive"))
      (node (ref "C158") (pin "1") (pinfunction "1_1") (pintype "passive"))
      (node (ref "C159") (pin "1") (pinfunction "1_1") (pintype "passive"))
      (node (ref "C160") (pin "1") (pinfunction "1_1") (pintype "passive"))
      (node (ref "L1") (pin "1") (pinfunction "1_1") (pintype "passive"))
      (node (ref "U3") (pin "1") (pinfunction "VDD_1") (pintype "power_in"))
      (node (ref "U3") (pin "14") (pinfunction "VDD_14") (pintype "power_in"))
      (node (ref "U3") (pin "27") (pinfunction "VDD_27") (pintype "power_in"))
      (node (ref "U3") (pin "3") (pinfunction "VDDQ_3") (pintype "power_in"))
      (node (ref "U3") (pin "43") (pinfunction "VDDQ_43") (pintype "power_in"))
      (node (ref "U3") (pin "49") (pinfunction "VDDQ_49") (pintype "power_in"))
      (node (ref "U3") (pin "9") (pinfunction "VDDQ_9") (pintype "power_in"))
      (node (ref "U4") (pin "1") (pinfunction "VDD_1") (pintype "power_in"))
      (node (ref "U4") (pin "14") (pinfunction "VDD_14") (pintype "power_in"))
      (node (ref "U4") (pin "27") (pinfunction "VDD_27") (pintype "power_in"))
      (node (ref "U4") (pin "3") (pinfunction "VDDQ_3") (pintype "power_in"))
      (node (ref "U4") (pin "43") (pinfunction "VDDQ_43") (pintype "power_in"))
      (node (ref "U4") (pin "49") (pinfunction "VDDQ_49") (pintype "power_in"))
      (node (ref "U4") (pin "9") (pinfunction "VDDQ_9") (pintype "power_in"))
      (node (ref "U5") (pin "1") (pinfunction "VDD_1") (pintype "power_in"))
      (node (ref "U5") (pin "14") (pinfunction "VDD_14") (pintype "power_in"))
      (node (ref "U5") (pin "27") (pinfunction "VDD_27") (pintype "power_in"))
      (node (ref "U5") (pin "3") (pinfunction "VDDQ_3") (pintype "power_in"))
      (node (ref "U5") (pin "43") (pinfunction "VDDQ_43") (pintype "power_in"))
      (node (ref "U5") (pin "49") (pinfunction "VDDQ_49") (pintype "power_in"))
      (node (ref "U5") (pin "9") (pinfunction "VDDQ_9") (pintype "power_in"))
      (node (ref "U6") (pin "1") (pinfunction "VDD_1") (pintype "power_in"))
      (node (ref "U6") (pin "14") (pinfunction "VDD_14") (pintype "power_in"))
      (node (ref "U6") (pin "27") (pinfunction "VDD_27") (pintype "power_in"))
      (node (ref "U6") (pin "3") (pinfunction "VDDQ_3") (pintype "power_in"))
      (node (ref "U6") (pin "43") (pinfunction "VDDQ_43") (pintype "power_in"))
      (node (ref "U6") (pin "49") (pinfunction "VDDQ_49") (pintype "power_in"))
      (node (ref "U6") (pin "9") (pinfunction "VDDQ_9") (pintype "power_in"))
      (node (ref "U7") (pin "1") (pinfunction "VDD_1") (pintype "power_in"))
      (node (ref "U7") (pin "14") (pinfunction "VDD_14") (pintype "power_in"))
      (node (ref "U7") (pin "27") (pinfunction "VDD_27") (pintype "power_in"))
      (node (ref "U7") (pin "3") (pinfunction "VDDQ_3") (pintype "power_in"))
      (node (ref "U7") (pin "43") (pinfunction "VDDQ_43") (pintype "power_in"))
      (node (ref "U7") (pin "49") (pinfunction "VDDQ_49") (pintype "power_in"))
      (node (ref "U7") (pin "9") (pinfunction "VDDQ_9") (pintype "power_in"))
      (node (ref "U8") (pin "1") (pinfunction "VDD_1") (pintype "power_in"))
      (node (ref "U8") (pin "14") (pinfunction "VDD_14") (pintype "power_in"))
      (node (ref "U8") (pin "27") (pinfunction "VDD_27") (pintype "power_in"))
      (node (ref "U8") (pin "3") (pinfunction "VDDQ_3") (pintype "power_in"))
      (node (ref "U8") (pin "43") (pinfunction "VDDQ_43") (pintype "power_in"))
      (node (ref "U8") (pin "49") (pinfunction "VDDQ_49") (pintype "power_in"))
      (node (ref "U8") (pin "9") (pinfunction "VDDQ_9") (pintype "power_in"))
    )
    (net (code "158") (name "P3V3_CLK") (class "Default")
      (node (ref "C161") (pin "2") (pinfunction "2_2") (pintype "passive"))
      (node (ref "C162") (pin "1") (pinfunction "1_1") (pintype "passive"))
      (node (ref "C163") (pin "1") (pinfunction "1_1") (pintype "passive"))
      (node (ref "C164") (pin "1") (pinfunction "1_1") (pintype "passive"))
      (node (ref "C165") (pin "1") (pinfunction "1_1") (pintype "passive"))
      (node (ref "C166") (pin "1") (pinfunction "1_1") (pintype "passive"))
      (node (ref "C167") (pin "1") (pinfunction "1_1") (pintype "passive"))
      (node (ref "IC7") (pin "10") (pinfunction "VDDO4_10") (pintype "passive"))
      (node (ref "IC7") (pin "15") (pinfunction "VDDO3_15") (pintype "passive"))
      (node (ref "IC7") (pin "18") (pinfunction "VDDO2_18") (pintype "passive"))
      (node (ref "IC7") (pin "21") (pinfunction "VDDO1_21") (pintype "passive"))
      (node (ref "IC7") (pin "22") (pinfunction "VDDD_22") (pintype "passive"))
      (node (ref "IC7") (pin "23") (pinfunction "VDDO0_23") (pintype "passive"))
      (node (ref "L1") (pin "2") (pinfunction "2_2") (pintype "passive"))
      (node (ref "R55") (pin "1") (pinfunction "1_1") (pintype "passive"))
      (node (ref "R59") (pin "1") (pinfunction "1_1") (pintype "passive"))
      (node (ref "R62") (pin "2") (pinfunction "2_2") (pintype "passive"))
    )
    (net (code "159") (name "unconnected-(IC7-OUT4-Pad11)") (class "Default")
      (node (ref "IC7") (pin "11") (pinfunction "OUT4_11") (pintype "passive"))
    )
    (net (code "160") (name "unconnected-(IC7-OUT4B-Pad12)") (class "Default")
      (node (ref "IC7") (pin "12") (pinfunction "OUT4B_12") (pintype "passive"))
    )
    (net (code "161") (name "unconnected-(IC7-SEL0{slash}SCL-Pad9)") (class "Default")
      (node (ref "IC7") (pin "9") (pinfunction "SEL0/SCL_9") (pintype "passive"))
    )
    (net (code "162") (name "unconnected-(IC7-SEL1{slash}SDA-Pad8)") (class "Default")
      (node (ref "IC7") (pin "8") (pinfunction "SEL1/SDA_8") (pintype "passive"))
    )
    (net (code "163") (name "unconnected-(IC7-XOUT-Pad3)") (class "Default")
      (node (ref "IC7") (pin "3") (pinfunction "XOUT_3") (pintype "passive"))
    )
    (net (code "164") (name "unconnected-(U3A-NC-Pad40)") (class "Default")
      (node (ref "U3") (pin "40") (pinfunction "NC_40") (pintype "passive"))
    )
    (net (code "165") (name "unconnected-(U4A-NC-Pad40)") (class "Default")
      (node (ref "U4") (pin "40") (pinfunction "NC_40") (pintype "passive"))
    )
    (net (code "166") (name "unconnected-(U5A-NC-Pad40)") (class "Default")
      (node (ref "U5") (pin "40") (pinfunction "NC_40") (pintype "passive"))
    )
    (net (code "167") (name "unconnected-(U6A-NC-Pad40)") (class "Default")
      (node (ref "U6") (pin "40") (pinfunction "NC_40") (pintype "passive"))
    )
    (net (code "168") (name "unconnected-(U7A-NC-Pad40)") (class "Default")
      (node (ref "U7") (pin "40") (pinfunction "NC_40") (pintype "passive"))
    )
    (net (code "169") (name "unconnected-(U8A-NC-Pad40)") (class "Default")
      (node (ref "U8") (pin "40") (pinfunction "NC_40") (pintype "passive"))
    )
  )
)
